# 425AK01A_S07.net
KiCad netlist of a schematic drawn in Altium Designer
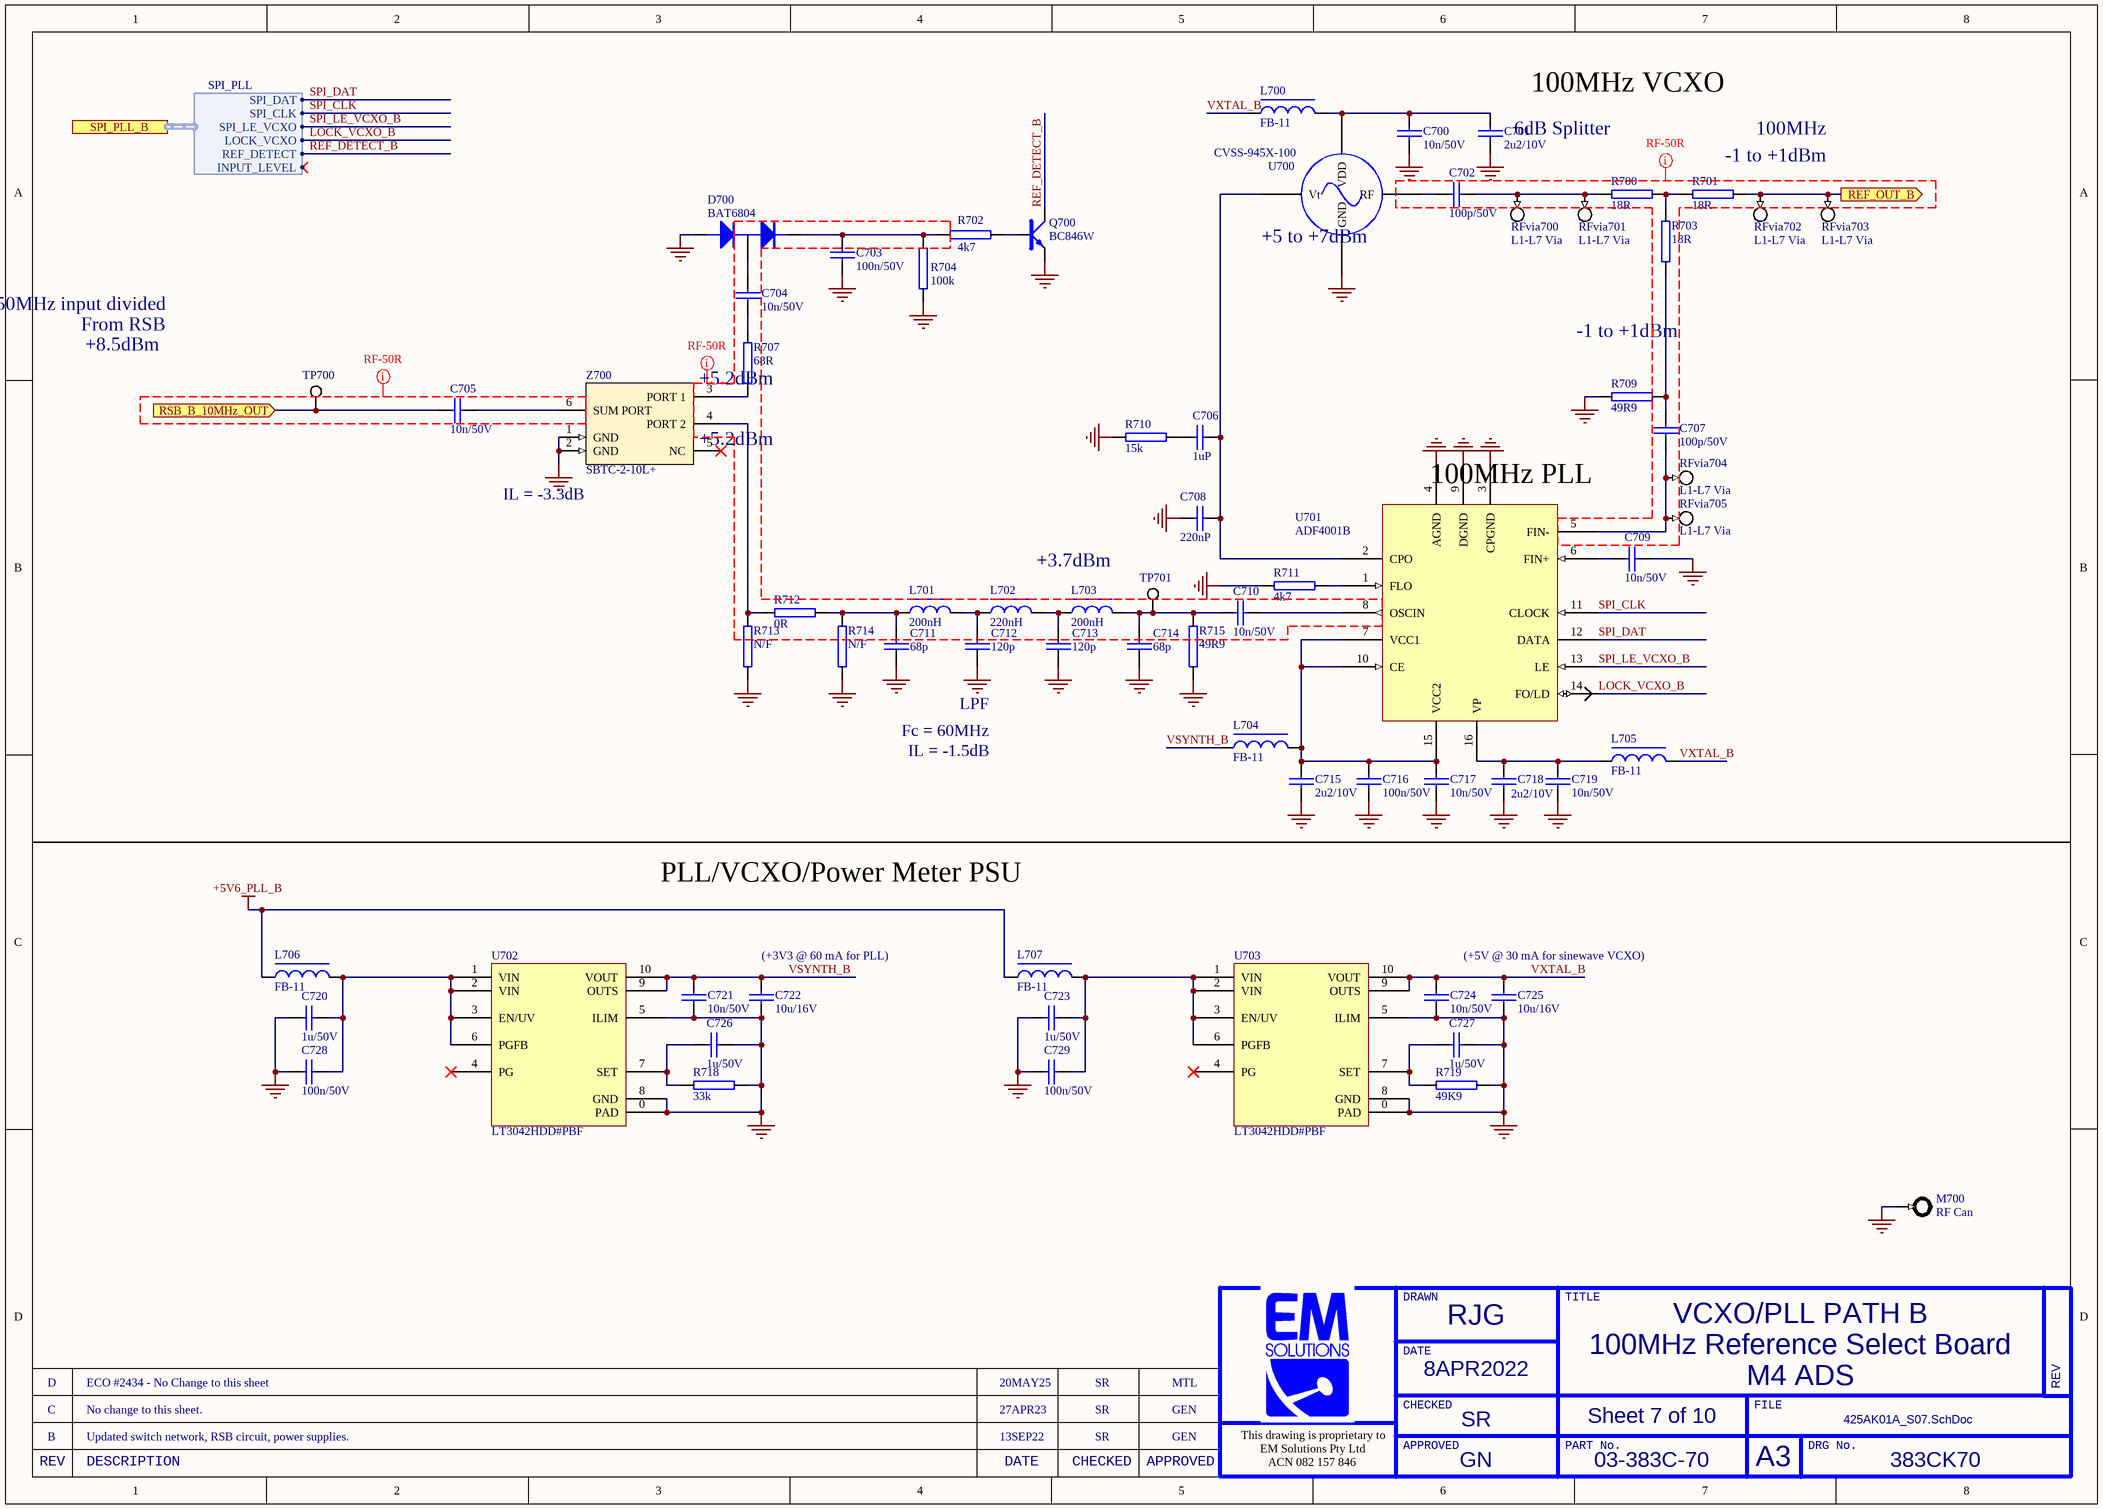
[diagram p0: 425AK01A_S07.SchDoc]

(export (version "E")
  (design (tool "Eeschema 10.0.6"))
  (components
    (comp (ref "C700")
      (value "10n/50V")
      (footprint "0402C")
      (description "Capacitor, 0402, 10n X7R 10% 50V Ceramic, NiSn")
      (fields (field (name "PART NUMBER") "41-010N-12") (field (name "MANUFACTURER") "MURATA"))
      (libsource (lib "EM DFM Library") (part "CAP"))
    )
    (comp (ref "C701")
      (value "2u2/10V")
      (footprint "0603C")
      (description "Capacitor, 0603, 2u2 X7R 10% 10V Ceramic, NiSn")
      (fields (field (name "PART NUMBER") "41-02U2-06") (field (name "MANUFACTURER") "MURATA"))
      (libsource (lib "EM DFM Library") (part "CAP"))
    )
    (comp (ref "C702")
      (value "100p/50V")
      (footprint "0402C")
      (description "Capacitor, 0402, 100p NPO 5% 50V Ceramic, AEC-Q200")
      (fields (field (name "PART NUMBER") "41-100P-11") (field (name "MANUFACTURER") "TDK"))
      (libsource (lib "EM DFM Library") (part "CAP"))
    )
    (comp (ref "C703")
      (value "100n/50V")
      (footprint "0402C")
      (description "Capacitor, 0402, 100n, X7R, 10% 50V, Ceramic")
      (fields (field (name "PART NUMBER") "41-100N-13") (field (name "MANUFACTURER") "MURATA"))
      (libsource (lib "EM DFM Library") (part "CAP"))
    )
    (comp (ref "C704")
      (value "10n/50V")
      (footprint "0402C")
      (description "Capacitor, 0402, 10n X7R 10% 50V Ceramic, NiSn")
      (fields (field (name "PART NUMBER") "41-010N-12") (field (name "MANUFACTURER") "MURATA"))
      (libsource (lib "EM DFM Library") (part "CAP"))
    )
    (comp (ref "C705")
      (value "10n/50V")
      (footprint "0402C")
      (description "Capacitor, 0402, 10n X7R 10% 50V Ceramic, NiSn")
      (fields (field (name "PART NUMBER") "41-010N-12") (field (name "MANUFACTURER") "MURATA"))
      (libsource (lib "EM DFM Library") (part "CAP"))
    )
    (comp (ref "C706")
      (value "1uP")
      (footprint "1210C")
      (description "Capacitor, 1210, 1u PPS 20% 16V Plastic Film")
      (fields (field (name "PART NUMBER") "41-01U0-05") (field (name "MANUFACTURER") "PANASONIC"))
      (libsource (lib "EM DFM Library") (part "CAP"))
    )
    (comp (ref "C707")
      (value "100p/50V")
      (footprint "0402C")
      (description "Capacitor, 0402, 100p NPO 5% 50V Ceramic, AEC-Q200")
      (fields (field (name "PART NUMBER") "41-100P-11") (field (name "MANUFACTURER") "TDK"))
      (libsource (lib "EM DFM Library") (part "CAP"))
    )
    (comp (ref "C708")
      (value "220nP")
      (footprint "1206C")
      (description "Capacitor, 1206, 220n PPS 20% 16V Plastic Film")
      (fields (field (name "PART NUMBER") "41-220N-05") (field (name "MANUFACTURER") "PANASONIC"))
      (libsource (lib "EM DFM Library") (part "CAP"))
    )
    (comp (ref "C709")
      (value "10n/50V")
      (footprint "0402C")
      (description "Capacitor, 0402, 10n X7R 10% 50V Ceramic, NiSn")
      (fields (field (name "PART NUMBER") "41-010N-12") (field (name "MANUFACTURER") "MURATA"))
      (libsource (lib "EM DFM Library") (part "CAP"))
    )
    (comp (ref "C710")
      (value "10n/50V")
      (footprint "0402C")
      (description "Capacitor, 0402, 10n X7R 10% 50V Ceramic, NiSn")
      (fields (field (name "PART NUMBER") "41-010N-12") (field (name "MANUFACTURER") "MURATA"))
      (libsource (lib "EM DFM Library") (part "CAP"))
    )
    (comp (ref "C711")
      (value "68p")
      (footprint "0402C")
      (description "Capacitor, 0402, 68p")
      (fields (field (name "PART NUMBER") "41-068P-08"))
      (libsource (lib "Russell") (part "41-068P-08"))
    )
    (comp (ref "C712")
      (value "120p")
      (footprint "0402C")
      (description "Capacitor, 0402, 120p NPO")
      (fields (field (name "PART NUMBER") "41-120P-05"))
      (libsource (lib "Russell") (part "41-120P-05"))
    )
    (comp (ref "C713")
      (value "120p")
      (footprint "0402C")
      (description "Capacitor, 0402, 120p NPO")
      (fields (field (name "PART NUMBER") "41-120P-05"))
      (libsource (lib "Russell") (part "41-120P-05"))
    )
    (comp (ref "C714")
      (value "68p")
      (footprint "0402C")
      (description "Capacitor, 0402, 68p")
      (fields (field (name "PART NUMBER") "41-068P-08"))
      (libsource (lib "Russell") (part "41-068P-08"))
    )
    (comp (ref "C715")
      (value "2u2/10V")
      (footprint "0603C")
      (description "Capacitor, 0603, 2u2 X7R 10% 10V Ceramic, NiSn")
      (fields (field (name "PART NUMBER") "41-02U2-06") (field (name "MANUFACTURER") "MURATA"))
      (libsource (lib "EM DFM Library") (part "CAP"))
    )
    (comp (ref "C716")
      (value "100n/50V")
      (footprint "0402C")
      (description "Capacitor, 0402, 100n, X7R, 10% 50V, Ceramic")
      (fields (field (name "PART NUMBER") "41-100N-13") (field (name "MANUFACTURER") "MURATA"))
      (libsource (lib "EM DFM Library") (part "CAP"))
    )
    (comp (ref "C717")
      (value "10n/50V")
      (footprint "0402C")
      (description "Capacitor, 0402, 10n X7R 10% 50V Ceramic, NiSn")
      (fields (field (name "PART NUMBER") "41-010N-12") (field (name "MANUFACTURER") "MURATA"))
      (libsource (lib "EM DFM Library") (part "CAP"))
    )
    (comp (ref "C718")
      (value "2u2/10V")
      (footprint "0603C")
      (description "Capacitor, 0603, 2u2 X7R 10% 10V Ceramic, NiSn")
      (fields (field (name "PART NUMBER") "41-02U2-06") (field (name "MANUFACTURER") "MURATA"))
      (libsource (lib "EM DFM Library") (part "CAP"))
    )
    (comp (ref "C719")
      (value "10n/50V")
      (footprint "0402C")
      (description "Capacitor, 0402, 10n X7R 10% 50V Ceramic, NiSn")
      (fields (field (name "PART NUMBER") "41-010N-12") (field (name "MANUFACTURER") "MURATA"))
      (libsource (lib "EM DFM Library") (part "CAP"))
    )
    (comp (ref "C720")
      (value "1u/50V")
      (footprint "0603C")
      (description "Capacitor, 0603, 1u X7R 10% 50V Ceramic, NiSn")
      (fields (field (name "PART NUMBER") "41-01U0-06") (field (name "MANUFACTURER") "TAIYOYUDEN"))
      (libsource (lib "EM DFM Library") (part "CAP"))
    )
    (comp (ref "C721")
      (value "10n/50V")
      (footprint "0402C")
      (description "Capacitor, 0402, 10n X7R 10% 50V Ceramic, NiSn")
      (fields (field (name "PART NUMBER") "41-010N-12") (field (name "MANUFACTURER") "MURATA"))
      (libsource (lib "EM DFM Library") (part "CAP"))
    )
    (comp (ref "C722")
      (value "10u/16V")
      (footprint "0805C")
      (description "Capacitor, 0805, 10u X7R 10% 16V Ceramic, NiSn")
      (fields (field (name "PART NUMBER") "41-010U-08") (field (name "MANUFACTURER") "SAMSUNG"))
      (libsource (lib "EM DFM Library") (part "CAP"))
    )
    (comp (ref "C723")
      (value "1u/50V")
      (footprint "0603C")
      (description "Capacitor, 0603, 1u X7R 10% 50V Ceramic, NiSn")
      (fields (field (name "PART NUMBER") "41-01U0-06") (field (name "MANUFACTURER") "TAIYOYUDEN"))
      (libsource (lib "EM DFM Library") (part "CAP"))
    )
    (comp (ref "C724")
      (value "10n/50V")
      (footprint "0402C")
      (description "Capacitor, 0402, 10n X7R 10% 50V Ceramic, NiSn")
      (fields (field (name "PART NUMBER") "41-010N-12") (field (name "MANUFACTURER") "MURATA"))
      (libsource (lib "EM DFM Library") (part "CAP"))
    )
    (comp (ref "C725")
      (value "10u/16V")
      (footprint "0805C")
      (description "Capacitor, 0805, 10u X7R 10% 16V Ceramic, NiSn")
      (fields (field (name "PART NUMBER") "41-010U-08") (field (name "MANUFACTURER") "SAMSUNG"))
      (libsource (lib "EM DFM Library") (part "CAP"))
    )
    (comp (ref "C726")
      (value "1u/50V")
      (footprint "0603C")
      (description "Capacitor, 0603, 1u X7R 10% 50V Ceramic, NiSn")
      (fields (field (name "PART NUMBER") "41-01U0-06") (field (name "MANUFACTURER") "TAIYOYUDEN"))
      (libsource (lib "EM DFM Library") (part "CAP"))
    )
    (comp (ref "C727")
      (value "1u/50V")
      (footprint "0603C")
      (description "Capacitor, 0603, 1u X7R 10% 50V Ceramic, NiSn")
      (fields (field (name "PART NUMBER") "41-01U0-06") (field (name "MANUFACTURER") "TAIYOYUDEN"))
      (libsource (lib "EM DFM Library") (part "CAP"))
    )
    (comp (ref "C728")
      (value "100n/50V")
      (footprint "0402C")
      (description "Capacitor, 0402, 100n, X7R, 10% 50V, Ceramic")
      (fields (field (name "PART NUMBER") "41-100N-13") (field (name "MANUFACTURER") "MURATA"))
      (libsource (lib "EM DFM Library") (part "CAP"))
    )
    (comp (ref "C729")
      (value "100n/50V")
      (footprint "0402C")
      (description "Capacitor, 0402, 100n, X7R, 10% 50V, Ceramic")
      (fields (field (name "PART NUMBER") "41-100N-13") (field (name "MANUFACTURER") "MURATA"))
      (libsource (lib "EM DFM Library") (part "CAP"))
    )
    (comp (ref "D700")
      (value "BAT6804")
      (footprint "SOT-23DAP")
      (description "*Diode, Schottky, Series Pair, 8V 130mA, SOT-23-3")
      (fields (field (name "PART NUMBER") "60-BAT68-04") (field (name "MANUFACTURER") "INFINEON"))
      (libsource (lib "EM DFM Library") (part "DIODE_AP2"))
    )
    (comp (ref "L700")
      (value "FB-11")
      (footprint "0402L")
      (description "Solid Inductor, 600ohm@100MHz, DCR=0.52, 0.3A, 0402 size")
      (fields (field (name "PART NUMBER") "46-B-11") (field (name "MANUFACTURER") "TDK"))
      (libsource (lib "EM DFM Library") (part "IND"))
    )
    (comp (ref "L701")
      (value "200nH")
      (footprint "0402L")
      (description "Inductor, Chip, 200nH, 0402")
      (fields (field (name "PART NUMBER") "46-200N-04"))
      (libsource (lib "Russell") (part "46-200N-04"))
    )
    (comp (ref "L702")
      (value "220nH")
      (footprint "0402L")
      (description "Inductor, Chip, 220nH, 0402")
      (fields (field (name "PART NUMBER") "46-220N-05"))
      (libsource (lib "Russell") (part "46-220N-05"))
    )
    (comp (ref "L703")
      (value "200nH")
      (footprint "0402L")
      (description "Inductor, Chip, 200nH, 0402")
      (fields (field (name "PART NUMBER") "46-200N-04"))
      (libsource (lib "Russell") (part "46-200N-04"))
    )
    (comp (ref "L704")
      (value "FB-11")
      (footprint "0402L")
      (description "Solid Inductor, 600ohm@100MHz, DCR=0.52, 0.3A, 0402 size")
      (fields (field (name "PART NUMBER") "46-B-11") (field (name "MANUFACTURER") "TDK"))
      (libsource (lib "EM DFM Library") (part "IND"))
    )
    (comp (ref "L705")
      (value "FB-11")
      (footprint "0402L")
      (description "Solid Inductor, 600ohm@100MHz, DCR=0.52, 0.3A, 0402 size")
      (fields (field (name "PART NUMBER") "46-B-11") (field (name "MANUFACTURER") "TDK"))
      (libsource (lib "EM DFM Library") (part "IND"))
    )
    (comp (ref "L706")
      (value "FB-11")
      (footprint "0402L")
      (description "Solid Inductor, 600ohm@100MHz, DCR=0.52, 0.3A, 0402 size")
      (fields (field (name "PART NUMBER") "46-B-11") (field (name "MANUFACTURER") "TDK"))
      (libsource (lib "") (part "IND_1"))
    )
    (comp (ref "L707")
      (value "FB-11")
      (footprint "0402L")
      (description "Solid Inductor, 600ohm@100MHz, DCR=0.52, 0.3A, 0402 size")
      (fields (field (name "PART NUMBER") "46-B-11") (field (name "MANUFACTURER") "TDK"))
      (libsource (lib "") (part "IND_1"))
    )
    (comp (ref "M700")
      (value "RF Can")
      (footprint "Can_38x25.4x6mm")
      (fields (field (name "PART NUMBER") "11-0256"))
      (libsource (lib "Russell") (part "Can-RF"))
    )
    (comp (ref "Q700")
      (value "BC846W")
      (footprint "SOT-323BJT")
      (description "Transistor, NPN Si, GenPur 65V 100mA, SOT-323")
      (fields (field (name "PART NUMBER") "62-BC846-01") (field (name "MANUFACTURER") "TAIWAN SEMI"))
      (libsource (lib "EM DFM Library") (part "NPN"))
    )
    (comp (ref "R700")
      (value "18R")
      (footprint "0402")
      (description "Resistor, 0402, 18R 1% 0.063W")
      (fields (field (name "PART NUMBER") "44-018R-10") (field (name "MANUFACTURER") "GENERIC"))
      (libsource (lib "EM DFM Library") (part "RES"))
    )
    (comp (ref "R701")
      (value "18R")
      (footprint "0402")
      (description "Resistor, 0402, 18R 1% 0.063W")
      (fields (field (name "PART NUMBER") "44-018R-10") (field (name "MANUFACTURER") "GENERIC"))
      (libsource (lib "EM DFM Library") (part "RES"))
    )
    (comp (ref "R702")
      (value "4k7")
      (footprint "0402")
      (description "Resistor, 0402, 4k7 1% 0.063W")
      (fields (field (name "PART NUMBER") "44-04K7-10") (field (name "MANUFACTURER") "PHILIPS"))
      (libsource (lib "EM DFM Library") (part "RES"))
    )
    (comp (ref "R703")
      (value "18R")
      (footprint "0402")
      (description "Resistor, 0402, 18R 1% 0.063W")
      (fields (field (name "PART NUMBER") "44-018R-10") (field (name "MANUFACTURER") "GENERIC"))
      (libsource (lib "EM DFM Library") (part "RES"))
    )
    (comp (ref "R704")
      (value "100k")
      (footprint "0402")
      (description "Resistor, 0402, 100k 1% 0.063W")
      (fields (field (name "PART NUMBER") "44-100K-10") (field (name "MANUFACTURER") "PHILIPS"))
      (libsource (lib "EM DFM Library") (part "RES"))
    )
    (comp (ref "R707")
      (value "68R")
      (footprint "0402")
      (description "Resistor, 0402, 68R 1% 0.063W")
      (fields (field (name "PART NUMBER") "44-068R-10") (field (name "MANUFACTURER") "PHILIPS"))
      (libsource (lib "EM DFM Library") (part "RES"))
    )
    (comp (ref "R709")
      (value "49R9")
      (footprint "0402")
      (description "Resistor, 0402, 49R9 1% 0.063W")
      (fields (field (name "PART NUMBER") "44-049R9-10") (field (name "MANUFACTURER") "YAGEO"))
      (libsource (lib "EM DFM Library") (part "RES"))
    )
    (comp (ref "R710")
      (value "15k")
      (footprint "0402")
      (description "Resistor, 0402, 15k 1% 0.063W")
      (fields (field (name "PART NUMBER") "44-015K-10") (field (name "MANUFACTURER") "PHILIPS"))
      (libsource (lib "EM DFM Library") (part "RES"))
    )
    (comp (ref "R711")
      (value "4k7")
      (footprint "0402")
      (description "Resistor, 0402, 4k7 1% 0.063W")
      (fields (field (name "PART NUMBER") "44-04K7-10") (field (name "MANUFACTURER") "PHILIPS"))
      (libsource (lib "EM DFM Library") (part "RES"))
    )
    (comp (ref "R712")
      (value "0R")
      (footprint "0402")
      (description "Resistor, 0402, 0R 1% 0.063W")
      (fields (field (name "PART NUMBER") "44-000R-10") (field (name "MANUFACTURER") "GENERIC"))
      (libsource (lib "EM DFM Library") (part "RES"))
    )
    (comp (ref "R713")
      (value "N/F")
      (footprint "0402")
      (description "Resistor, 0402, SOT, Not Fitted")
      (fields (field (name "PART NUMBER") "44-N/F-10"))
      (libsource (lib "EM DFM Library") (part "RES"))
    )
    (comp (ref "R714")
      (value "N/F")
      (footprint "0402")
      (description "Resistor, 0402, SOT, Not Fitted")
      (fields (field (name "PART NUMBER") "44-N/F-10"))
      (libsource (lib "EM DFM Library") (part "RES"))
    )
    (comp (ref "R715")
      (value "49R9")
      (footprint "0402")
      (description "Resistor, 0402, 49R9 1% 0.063W")
      (fields (field (name "PART NUMBER") "44-049R9-10") (field (name "MANUFACTURER") "YAGEO"))
      (libsource (lib "EM DFM Library") (part "RES"))
    )
    (comp (ref "R718")
      (value "33k")
      (footprint "0402")
      (description "Resistor, 0402, 33k 1% 0.063W")
      (fields (field (name "PART NUMBER") "44-033K-10") (field (name "MANUFACTURER") "PHILIPS"))
      (libsource (lib "EM DFM Library") (part "RES"))
    )
    (comp (ref "R719")
      (value "49K9")
      (footprint "0402")
      (description "Resistor, 0402, 49.9K, 1%, 0.1W, ThickFilm, AEC-Q200")
      (fields (field (name "PART NUMBER") "44-49K9-01") (field (name "MANUFACTURER") "PANASONIC"))
      (libsource (lib "EM DFM Library") (part "RES"))
    )
    (comp (ref "RFvia700")
      (value "L1-L7 Via")
      (footprint "RFvia_L1-L7")
      (description "RF Via from layer 1 to layer 7, on an 8-layer board.")
      (libsource (lib "RFvias-8layer") (part "RFvia_L1-L7"))
    )
    (comp (ref "RFvia701")
      (value "L1-L7 Via")
      (footprint "RFvia_L1-L7")
      (description "RF Via from layer 1 to layer 7, on an 8-layer board.")
      (libsource (lib "RFvias-8layer") (part "RFvia_L1-L7"))
    )
    (comp (ref "RFvia702")
      (value "L1-L7 Via")
      (footprint "RFvia_L1-L7")
      (description "RF Via from layer 1 to layer 7, on an 8-layer board.")
      (libsource (lib "RFvias-8layer") (part "RFvia_L1-L7"))
    )
    (comp (ref "RFvia703")
      (value "L1-L7 Via")
      (footprint "RFvia_L1-L7")
      (description "RF Via from layer 1 to layer 7, on an 8-layer board.")
      (libsource (lib "RFvias-8layer") (part "RFvia_L1-L7"))
    )
    (comp (ref "RFvia704")
      (value "L1-L7 Via")
      (footprint "RFvia_L1-L7")
      (description "RF Via from layer 1 to layer 7, on an 8-layer board.")
      (libsource (lib "RFvias-8layer") (part "RFvia_L1-L7"))
    )
    (comp (ref "RFvia705")
      (value "L1-L7 Via")
      (footprint "RFvia_L1-L7")
      (description "RF Via from layer 1 to layer 7, on an 8-layer board.")
      (libsource (lib "RFvias-8layer") (part "RFvia_L1-L7"))
    )
    (comp (ref "TP700")
      (value "Pad")
      (footprint "Testpoint-0.5mm-SMT-withPaste")
      (description "Pad that can be a test point or a hot via")
      (libsource (lib "Russell") (part "Pad"))
    )
    (comp (ref "TP701")
      (value "Pad")
      (footprint "Testpoint-0.5mm-SMT-withPaste")
      (description "Pad that can be a test point or a hot via")
      (libsource (lib "Russell") (part "Pad"))
    )
    (comp (ref "U700")
      (value "CVSS-945X-100")
      (footprint "CVHD-950")
      (description "VCXO, 100.00MHz, Sine 5V, SMD")
      (fields (field (name "PART NUMBER") "35-0223") (field (name "MANUFACTURER") "CRYSTEK"))
      (libsource (lib "EM DFM Library") (part "CVHD-950X-100"))
    )
    (comp (ref "U701")
      (value "ADF4001B")
      (footprint "TSSOP-16")
      (description "PLL Clock Gen, 200MHz, Serial TSSOP-16")
      (fields (field (name "PART NUMBER") "54-4001-01") (field (name "MANUFACTURER") "ANLG DEV"))
      (libsource (lib "EM DFM Library") (part "ADF4001BRUZ"))
    )
    (comp (ref "U702")
      (value "LT3042HDD#PBF")
      (footprint "DFN50P300X300X80_HS-11N")
      (description "Volt Regulator, Vin=1.8-20V, Vin=0-15V, 200mA, Low Noise, -40to+125C")
      (fields (field (name "PART NUMBER") "52-3042-01") (field (name "MANUFACTURER") "ANLG DEV"))
      (libsource (lib "EM DFM Library") (part "LT3042"))
    )
    (comp (ref "U703")
      (value "LT3042HDD#PBF")
      (footprint "DFN50P300X300X80_HS-11N")
      (description "Volt Regulator, Vin=1.8-20V, Vin=0-15V, 200mA, Low Noise, -40to+125C")
      (fields (field (name "PART NUMBER") "52-3042-01") (field (name "MANUFACTURER") "ANLG DEV"))
      (libsource (lib "EM DFM Library") (part "LT3042"))
    )
    (comp (ref "Z700")
      (value "SBTC-2-10L+")
      (footprint "SBTC-2-10L+")
      (description "Divider/Combiner, 2 Way, 0 deg, 10 -1000MHz, Tx Line Tranformer")
      (fields (field (name "PART NUMBER") "33-0055") (field (name "MANUFACTURER") "MINICCTS"))
      (libsource (lib "EM DFM Library") (part "SBTC-2-10L+"))
    )
  )
  (nets
    (net (code "2") (name "+5V6_PLL_B") (class "Default")
      (node (ref "L706") (pin "2") (pinfunction "2_2") (pintype "passive"))
      (node (ref "L707") (pin "2") (pinfunction "2_2") (pintype "passive"))
    )
    (net (code "3") (name "/LOCK_VCXO_B") (class "Default")
      (node (ref "U701") (pin "14") (pinfunction "FO/LD_14") (pintype "bidirectional"))
    )
    (net (code "4") (name "/REF_DETECT_B") (class "Default")
      (node (ref "Q700") (pin "C") (pinfunction "C_C") (pintype "passive"))
    )
    (net (code "5") (name "/REF_OUT_B") (class "Default")
      (node (ref "R701") (pin "2") (pintype "passive"))
      (node (ref "RFvia702") (pin "1") (pinfunction "1_1") (pintype "input"))
      (node (ref "RFvia703") (pin "1") (pinfunction "1_1") (pintype "input"))
    )
    (net (code "6") (name "/RSB_B_10MHz_OUT") (class "Default")
      (node (ref "C705") (pin "1") (pintype "passive"))
      (node (ref "TP700") (pin "1") (pinfunction "1_1") (pintype "passive"))
    )
    (net (code "7") (name "/SPI_CLK") (class "Default")
      (node (ref "U701") (pin "11") (pinfunction "CLOCK_11") (pintype "input"))
    )
    (net (code "8") (name "/SPI_DAT") (class "Default")
      (node (ref "U701") (pin "12") (pinfunction "DATA_12") (pintype "passive"))
    )
    (net (code "9") (name "/SPI_LE_VCXO_B") (class "Default")
      (node (ref "U701") (pin "13") (pinfunction "LE_13") (pintype "input"))
    )
    (net (code "10") (name "/VSYNTH_B") (class "Default")
      (node (ref "C721") (pin "2") (pintype "passive"))
      (node (ref "C722") (pin "1") (pintype "passive"))
      (node (ref "L704") (pin "1") (pinfunction "1_1") (pintype "passive"))
      (node (ref "U702") (pin "10") (pinfunction "VOUT_10") (pintype "passive"))
      (node (ref "U702") (pin "9") (pinfunction "OUTS_9") (pintype "passive"))
    )
    (net (code "11") (name "/VXTAL_B") (class "Default")
      (node (ref "C724") (pin "2") (pintype "passive"))
      (node (ref "C725") (pin "1") (pintype "passive"))
      (node (ref "L700") (pin "1") (pinfunction "1_1") (pintype "passive"))
      (node (ref "L705") (pin "2") (pinfunction "2_2") (pintype "passive"))
      (node (ref "U703") (pin "10") (pinfunction "VOUT_10") (pintype "passive"))
      (node (ref "U703") (pin "9") (pinfunction "OUTS_9") (pintype "passive"))
    )
    (net (code "13") (name "GND") (class "Default")
      (node (ref "C700") (pin "2") (pintype "passive"))
      (node (ref "C701") (pin "2") (pintype "passive"))
      (node (ref "C703") (pin "1") (pintype "passive"))
      (node (ref "C708") (pin "1") (pintype "passive"))
      (node (ref "C709") (pin "2") (pintype "passive"))
      (node (ref "C711") (pin "1") (pintype "passive"))
      (node (ref "C712") (pin "1") (pintype "passive"))
      (node (ref "C713") (pin "1") (pintype "passive"))
      (node (ref "C714") (pin "1") (pintype "passive"))
      (node (ref "C715") (pin "2") (pintype "passive"))
      (node (ref "C716") (pin "2") (pintype "passive"))
      (node (ref "C717") (pin "2") (pintype "passive"))
      (node (ref "C718") (pin "2") (pintype "passive"))
      (node (ref "C719") (pin "2") (pintype "passive"))
      (node (ref "C720") (pin "1") (pintype "passive"))
      (node (ref "C721") (pin "1") (pintype "passive"))
      (node (ref "C722") (pin "2") (pintype "passive"))
      (node (ref "C723") (pin "1") (pintype "passive"))
      (node (ref "C724") (pin "1") (pintype "passive"))
      (node (ref "C725") (pin "2") (pintype "passive"))
      (node (ref "C726") (pin "2") (pintype "passive"))
      (node (ref "C727") (pin "2") (pintype "passive"))
      (node (ref "C728") (pin "2") (pintype "passive"))
      (node (ref "C729") (pin "2") (pintype "passive"))
      (node (ref "D700") (pin "A") (pintype "passive"))
      (node (ref "M700") (pin "0") (pinfunction "0_0") (pintype "input"))
      (node (ref "Q700") (pin "E") (pinfunction "E_E") (pintype "passive"))
      (node (ref "R704") (pin "1") (pintype "passive"))
      (node (ref "R709") (pin "2") (pintype "passive"))
      (node (ref "R710") (pin "2") (pintype "passive"))
      (node (ref "R711") (pin "1") (pintype "passive"))
      (node (ref "R713") (pin "1") (pintype "passive"))
      (node (ref "R714") (pin "1") (pintype "passive"))
      (node (ref "R715") (pin "1") (pintype "passive"))
      (node (ref "R718") (pin "1") (pintype "passive"))
      (node (ref "R719") (pin "1") (pintype "passive"))
      (node (ref "U700") (pin "2") (pinfunction "GND_2") (pintype "passive"))
      (node (ref "U701") (pin "3") (pinfunction "CPGND_3") (pintype "passive"))
      (node (ref "U701") (pin "4") (pinfunction "AGND_4") (pintype "passive"))
      (node (ref "U701") (pin "9") (pinfunction "DGND_9") (pintype "passive"))
      (node (ref "U702") (pin "0") (pinfunction "PAD_0") (pintype "passive"))
      (node (ref "U702") (pin "5") (pinfunction "ILIM_5") (pintype "passive"))
      (node (ref "U702") (pin "8") (pinfunction "GND_8") (pintype "passive"))
      (node (ref "U703") (pin "0") (pinfunction "PAD_0") (pintype "passive"))
      (node (ref "U703") (pin "5") (pinfunction "ILIM_5") (pintype "passive"))
      (node (ref "U703") (pin "8") (pinfunction "GND_8") (pintype "passive"))
      (node (ref "Z700") (pin "1") (pinfunction "GND_1") (pintype "input"))
      (node (ref "Z700") (pin "2") (pinfunction "GND_2") (pintype "input"))
    )
    (net (code "14") (name "Net-(C702-Pad1)") (class "Default")
      (node (ref "C702") (pin "1") (pintype "passive"))
      (node (ref "R700") (pin "1") (pintype "passive"))
      (node (ref "RFvia700") (pin "1") (pinfunction "1_1") (pintype "input"))
      (node (ref "RFvia701") (pin "1") (pinfunction "1_1") (pintype "input"))
    )
    (net (code "15") (name "Net-(C703-Pad2)") (class "Default")
      (node (ref "C703") (pin "2") (pintype "passive"))
      (node (ref "D700") (pin "K") (pintype "passive"))
      (node (ref "R702") (pin "2") (pintype "passive"))
      (node (ref "R704") (pin "2") (pintype "passive"))
    )
    (net (code "16") (name "Net-(C704-Pad1)") (class "Default")
      (node (ref "C704") (pin "1") (pintype "passive"))
      (node (ref "R707") (pin "2") (pintype "passive"))
    )
    (net (code "17") (name "Net-(C704-Pad2)") (class "Default")
      (node (ref "C704") (pin "2") (pintype "passive"))
      (node (ref "D700") (pin "KA") (pintype "passive"))
    )
    (net (code "18") (name "Net-(C706-Pad2)") (class "Default")
      (node (ref "C706") (pin "2") (pintype "passive"))
      (node (ref "R710") (pin "1") (pintype "passive"))
    )
    (net (code "19") (name "Net-(C707-Pad1)") (class "Default")
      (node (ref "C707") (pin "1") (pintype "passive"))
      (node (ref "R703") (pin "2") (pintype "passive"))
      (node (ref "R709") (pin "1") (pintype "passive"))
    )
    (net (code "20") (name "Net-(C710-Pad1)") (class "Default")
      (node (ref "C710") (pin "1") (pintype "passive"))
      (node (ref "C714") (pin "2") (pintype "passive"))
      (node (ref "L703") (pin "2") (pinfunction "2_2") (pintype "passive"))
      (node (ref "R715") (pin "2") (pintype "passive"))
      (node (ref "TP701") (pin "1") (pinfunction "1_1") (pintype "passive"))
    )
    (net (code "21") (name "Net-(C711-Pad2)") (class "Default")
      (node (ref "C711") (pin "2") (pintype "passive"))
      (node (ref "L701") (pin "1") (pinfunction "1_1") (pintype "passive"))
      (node (ref "R712") (pin "1") (pintype "passive"))
      (node (ref "R714") (pin "2") (pintype "passive"))
    )
    (net (code "22") (name "Net-(C712-Pad2)") (class "Default")
      (node (ref "C712") (pin "2") (pintype "passive"))
      (node (ref "L701") (pin "2") (pinfunction "2_2") (pintype "passive"))
      (node (ref "L702") (pin "1") (pinfunction "1_1") (pintype "passive"))
    )
    (net (code "23") (name "Net-(C713-Pad2)") (class "Default")
      (node (ref "C713") (pin "2") (pintype "passive"))
      (node (ref "L702") (pin "2") (pinfunction "2_2") (pintype "passive"))
      (node (ref "L703") (pin "1") (pinfunction "1_1") (pintype "passive"))
    )
    (net (code "24") (name "Net-(Q700-PadB)") (class "Default")
      (node (ref "Q700") (pin "B") (pinfunction "B_B") (pintype "passive"))
      (node (ref "R702") (pin "1") (pintype "passive"))
    )
    (net (code "25") (name "Net-(R700-Pad2)") (class "Default")
      (node (ref "R700") (pin "2") (pintype "passive"))
      (node (ref "R701") (pin "1") (pintype "passive"))
      (node (ref "R703") (pin "1") (pintype "passive"))
    )
    (net (code "26") (name "Net-(U700-RF)") (class "Default")
      (node (ref "C702") (pin "2") (pintype "passive"))
      (node (ref "U700") (pin "3") (pinfunction "RF_3") (pintype "passive"))
    )
    (net (code "27") (name "Net-(U700-VDD)") (class "Default")
      (node (ref "C700") (pin "1") (pintype "passive"))
      (node (ref "C701") (pin "1") (pintype "passive"))
      (node (ref "L700") (pin "2") (pinfunction "2_2") (pintype "passive"))
      (node (ref "U700") (pin "4") (pinfunction "VDD_4") (pintype "passive"))
    )
    (net (code "28") (name "Net-(U700-Vt)") (class "Default")
      (node (ref "C706") (pin "1") (pintype "passive"))
      (node (ref "C708") (pin "2") (pintype "passive"))
      (node (ref "U700") (pin "1") (pinfunction "Vt_1") (pintype "passive"))
      (node (ref "U701") (pin "2") (pinfunction "CPO_2") (pintype "passive"))
    )
    (net (code "29") (name "Net-(U701-CE)") (class "Default")
      (node (ref "C715") (pin "1") (pintype "passive"))
      (node (ref "C716") (pin "1") (pintype "passive"))
      (node (ref "C717") (pin "1") (pintype "passive"))
      (node (ref "L704") (pin "2") (pinfunction "2_2") (pintype "passive"))
      (node (ref "U701") (pin "10") (pinfunction "CE_10") (pintype "input"))
      (node (ref "U701") (pin "15") (pinfunction "VCC2_15") (pintype "power_in"))
      (node (ref "U701") (pin "7") (pinfunction "VCC1_7") (pintype "power_in"))
    )
    (net (code "30") (name "Net-(U701-FIN+)") (class "Default")
      (node (ref "C709") (pin "1") (pintype "passive"))
      (node (ref "U701") (pin "6") (pinfunction "FIN+_6") (pintype "input"))
    )
    (net (code "31") (name "Net-(U701-FIN-)") (class "Default")
      (node (ref "C707") (pin "2") (pintype "passive"))
      (node (ref "RFvia704") (pin "1") (pinfunction "1_1") (pintype "input"))
      (node (ref "RFvia705") (pin "1") (pinfunction "1_1") (pintype "input"))
      (node (ref "U701") (pin "5") (pinfunction "FIN-_5") (pintype "power_in"))
    )
    (net (code "32") (name "Net-(U701-FLO)") (class "Default")
      (node (ref "R711") (pin "2") (pintype "passive"))
      (node (ref "U701") (pin "1") (pinfunction "FLO_1") (pintype "input"))
    )
    (net (code "33") (name "Net-(U701-OSCIN)") (class "Default")
      (node (ref "C710") (pin "2") (pintype "passive"))
      (node (ref "U701") (pin "8") (pinfunction "OSCIN_8") (pintype "output"))
    )
    (net (code "34") (name "Net-(U701-VP)") (class "Default")
      (node (ref "C718") (pin "1") (pintype "passive"))
      (node (ref "C719") (pin "1") (pintype "passive"))
      (node (ref "L705") (pin "1") (pinfunction "1_1") (pintype "passive"))
      (node (ref "U701") (pin "16") (pinfunction "VP_16") (pintype "power_in"))
    )
    (net (code "35") (name "Net-(U702-EN{slash}UV)") (class "Default")
      (node (ref "C720") (pin "2") (pintype "passive"))
      (node (ref "C728") (pin "1") (pintype "passive"))
      (node (ref "L706") (pin "1") (pinfunction "1_1") (pintype "passive"))
      (node (ref "U702") (pin "1") (pinfunction "VIN_1") (pintype "passive"))
      (node (ref "U702") (pin "2") (pinfunction "VIN_2") (pintype "passive"))
      (node (ref "U702") (pin "3") (pinfunction "EN/UV_3") (pintype "passive"))
      (node (ref "U702") (pin "6") (pinfunction "PGFB_6") (pintype "passive"))
    )
    (net (code "36") (name "Net-(U702-SET)") (class "Default")
      (node (ref "C726") (pin "1") (pintype "passive"))
      (node (ref "R718") (pin "2") (pintype "passive"))
      (node (ref "U702") (pin "7") (pinfunction "SET_7") (pintype "passive"))
    )
    (net (code "37") (name "Net-(U703-EN{slash}UV)") (class "Default")
      (node (ref "C723") (pin "2") (pintype "passive"))
      (node (ref "C729") (pin "1") (pintype "passive"))
      (node (ref "L707") (pin "1") (pinfunction "1_1") (pintype "passive"))
      (node (ref "U703") (pin "1") (pinfunction "VIN_1") (pintype "passive"))
      (node (ref "U703") (pin "2") (pinfunction "VIN_2") (pintype "passive"))
      (node (ref "U703") (pin "3") (pinfunction "EN/UV_3") (pintype "passive"))
      (node (ref "U703") (pin "6") (pinfunction "PGFB_6") (pintype "passive"))
    )
    (net (code "38") (name "Net-(U703-SET)") (class "Default")
      (node (ref "C727") (pin "1") (pintype "passive"))
      (node (ref "R719") (pin "2") (pintype "passive"))
      (node (ref "U703") (pin "7") (pinfunction "SET_7") (pintype "passive"))
    )
    (net (code "39") (name "Net-(Z700-PORT_1)") (class "Default")
      (node (ref "R707") (pin "1") (pintype "passive"))
      (node (ref "Z700") (pin "3") (pinfunction "PORT_1_3") (pintype "passive"))
    )
    (net (code "40") (name "Net-(Z700-PORT_2)") (class "Default")
      (node (ref "R712") (pin "2") (pintype "passive"))
      (node (ref "R713") (pin "2") (pintype "passive"))
      (node (ref "Z700") (pin "4") (pinfunction "PORT_2_4") (pintype "passive"))
    )
    (net (code "41") (name "Net-(Z700-SUM_PORT)") (class "Default")
      (node (ref "C705") (pin "2") (pintype "passive"))
      (node (ref "Z700") (pin "6") (pinfunction "SUM_PORT_6") (pintype "passive"))
    )
    (net (code "42") (name "unconnected-(U702-PG-Pad4)") (class "Default")
      (node (ref "U702") (pin "4") (pinfunction "PG_4") (pintype "passive+no_connect"))
    )
    (net (code "43") (name "unconnected-(U703-PG-Pad4)") (class "Default")
      (node (ref "U703") (pin "4") (pinfunction "PG_4") (pintype "passive+no_connect"))
    )
    (net (code "44") (name "unconnected-(Z700-NC-Pad5)") (class "Default")
      (node (ref "Z700") (pin "5") (pinfunction "NC_5") (pintype "passive+no_connect"))
    )
  )
)
